# 3_waffling60-MX_mcu.net
KiCad netlist of a schematic drawn in Altium Designer
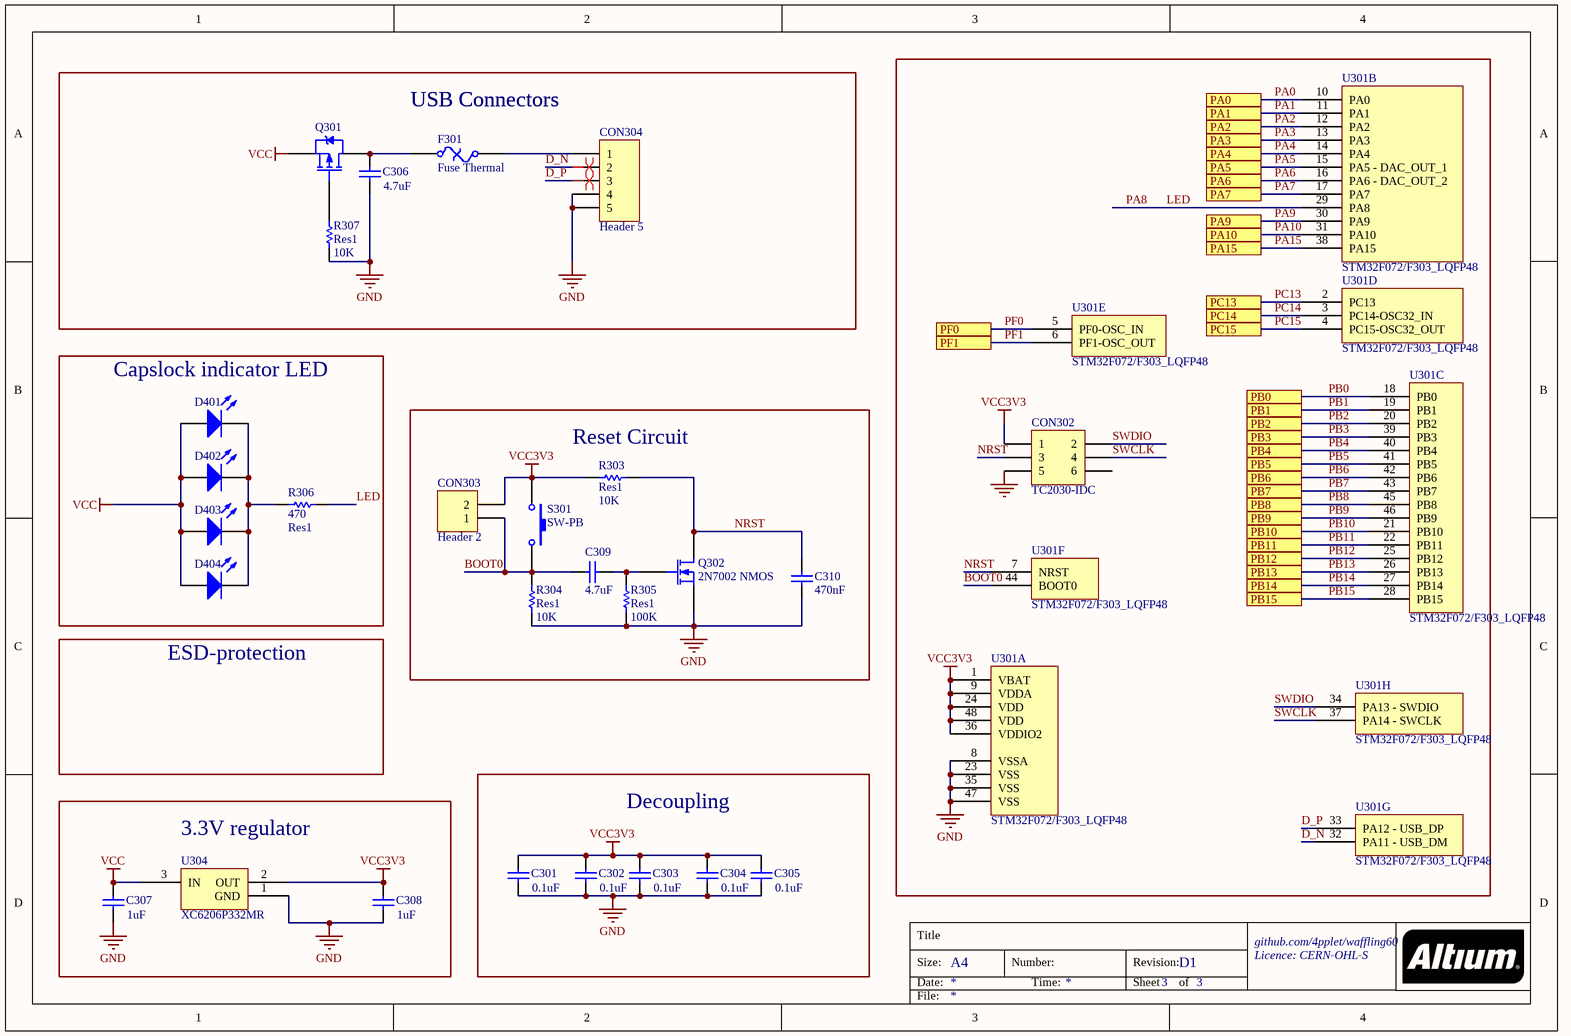
[diagram p0: 3_waffling60-MX_mcu.SchDoc]

(export (version "E")
  (design (tool "Eeschema 10.0.6"))
  (components
    (comp (ref "C301")
      (value "0.1uF")
      (footprint "C0603[1608]")
      (description "Capacitor")
      (fields (field (name "LCSC PART #") "C14663") (field (name "MRF.PART") "CC0603KRX7R9BB104"))
      (libsource (lib "Miscellaneous Devices") (part "Cap"))
    )
    (comp (ref "C302")
      (value "0.1uF")
      (footprint "C0603[1608]")
      (description "Capacitor")
      (fields (field (name "LCSC PART #") "C14663") (field (name "MRF.PART") "CC0603KRX7R9BB104"))
      (libsource (lib "Miscellaneous Devices") (part "Cap"))
    )
    (comp (ref "C303")
      (value "0.1uF")
      (footprint "C0603[1608]")
      (description "Capacitor")
      (fields (field (name "LCSC PART #") "C14663") (field (name "MRF.PART") "CC0603KRX7R9BB104"))
      (libsource (lib "Miscellaneous Devices") (part "Cap"))
    )
    (comp (ref "C304")
      (value "0.1uF")
      (footprint "C0603[1608]")
      (description "Capacitor")
      (fields (field (name "LCSC PART #") "C14663") (field (name "MRF.PART") "CC0603KRX7R9BB104"))
      (libsource (lib "Miscellaneous Devices") (part "Cap"))
    )
    (comp (ref "C305")
      (value "0.1uF")
      (footprint "C0603[1608]")
      (description "Capacitor")
      (fields (field (name "LCSC PART #") "C14663") (field (name "MRF.PART") "CC0603KRX7R9BB104"))
      (libsource (lib "Miscellaneous Devices") (part "Cap"))
    )
    (comp (ref "C306")
      (value "4.7uF")
      (footprint "C0603[1608]")
      (description "Capacitor")
      (fields (field (name "LCSC PART #") "C19666") (field (name "MRF.PART") "CL10A475KO8NNNC"))
      (libsource (lib "Miscellaneous Devices") (part "Cap"))
    )
    (comp (ref "C307")
      (value "1uF")
      (footprint "C0603[1608]")
      (description "Capacitor")
      (fields (field (name "LCSC PART #") "C15849") (field (name "MRF.PART") "CL10A105KB8NNNC"))
      (libsource (lib "Miscellaneous Devices") (part "Cap"))
    )
    (comp (ref "C308")
      (value "1uF")
      (footprint "C0603[1608]")
      (description "Capacitor")
      (fields (field (name "LCSC PART #") "C15849") (field (name "MRF.PART") "CL10A105KB8NNNC"))
      (libsource (lib "Miscellaneous Devices") (part "Cap"))
    )
    (comp (ref "C309")
      (value "4.7uF")
      (footprint "C0603[1608]")
      (description "Capacitor")
      (fields (field (name "LCSC PART #") "C19666") (field (name "MRF.PART") "CL10A475KO8NNNC"))
      (libsource (lib "Miscellaneous Devices") (part "Cap"))
    )
    (comp (ref "C310")
      (value "470nF")
      (footprint "C0603[1608]")
      (description "Capacitor")
      (fields (field (name "LCSC PART #") "C1623") (field (name "MRF.PART") "CL10B474KA8NNNC"))
      (libsource (lib "Miscellaneous Devices") (part "Cap"))
    )
    (comp (ref "CON302")
      (value "TC2030-IDC")
      (footprint "TC2030-IDC-NL")
      (description "Header, 3-Pin, Dual row")
      (libsource (lib "Miscellaneous Connectors") (part "Header 3X2"))
    )
    (comp (ref "CON303")
      (value "Header 2")
      (footprint "HDR1X2")
      (description "Header, 2-Pin")
      (libsource (lib "Miscellaneous Connectors") (part "Header 2"))
    )
    (comp (ref "CON304")
      (value "Header 5")
      (footprint "JST SM04B-SRSS-TB")
      (description "JST for USB daughter board")
      (fields (field (name "LCSC PART #") "C160404") (field (name "MRF.PART") "SM04B-SRSS-TB(LF)(SN)"))
      (libsource (lib "Miscellaneous Connectors") (part "Header 5"))
    )
    (comp (ref "D401")
      (value "CAPS_LED")
      (footprint "SWITCH_LED - 1U")
      (libsource (lib "Simulation Generic Components") (part "LED"))
    )
    (comp (ref "D402")
      (value "CAPS_LED")
      (footprint "SWITCH_LED - 1U")
      (libsource (lib "Simulation Generic Components") (part "LED"))
    )
    (comp (ref "D403")
      (value "CAPS_LED")
      (footprint "SWITCH_LED - 1U")
      (libsource (lib "Simulation Generic Components") (part "LED"))
    )
    (comp (ref "D404")
      (value "CAPS_LED")
      (footprint "SWITCH_LED - 1U")
      (libsource (lib "Simulation Generic Components") (part "LED"))
    )
    (comp (ref "F301")
      (value "Fuse Thermal")
      (footprint "C1206[3216]")
      (description "Thermal Fuse")
      (fields (field (name "LCSC PART #") "C135338") (field (name "MRF.PART") "ASMD1206-050"))
      (libsource (lib "Miscellaneous Devices") (part "Fuse Thermal"))
    )
    (comp (ref "Q301")
      (value "PMOS-2")
      (footprint "SOT-23-3")
      (description "P-Channel Power MOSFET")
      (fields (field (name "LCSC PART #") "C10487") (field (name "MRF.PART") "SI2301CDS-T1-GE3"))
      (libsource (lib "Miscellaneous Devices") (part "PMOS-2"))
    )
    (comp (ref "Q302")
      (value "2N7002 NMOS")
      (footprint "SOT-23-3")
      (description "N-Channel MOSFET")
      (fields (field (name "LCSC PART #") "C8545") (field (name "MRF.PART") "2N7002"))
      (libsource (lib "Miscellaneous Devices") (part "MOSFET-N"))
    )
    (comp (ref "R303")
      (value "Res1")
      (footprint "R0603[1608]")
      (description "Resistor")
      (fields
        (field (name "ALTIUM_VALUE") "10K")
        (field (name "LCSC PART #") "C25804")
        (field (name "MRF.PART") "0603WAF1002T5E")
      )
      (libsource (lib "Miscellaneous Devices") (part "Res1"))
    )
    (comp (ref "R304")
      (value "Res1")
      (footprint "R0603[1608]")
      (description "Resistor")
      (fields
        (field (name "ALTIUM_VALUE") "10K")
        (field (name "LCSC PART #") "C25804")
        (field (name "MRF.PART") "0603WAF1002T5E")
      )
      (libsource (lib "Miscellaneous Devices") (part "Res1"))
    )
    (comp (ref "R305")
      (value "Res1")
      (footprint "R0603[1608]")
      (description "Resistor")
      (fields
        (field (name "ALTIUM_VALUE") "100K")
        (field (name "LCSC PART #") "C25803")
        (field (name "MRF.PART") "0603WAF1003T5E")
      )
      (libsource (lib "Miscellaneous Devices") (part "Res1"))
    )
    (comp (ref "R306")
      (value "Res1")
      (footprint "R0603[1608]")
      (description "Resistor")
      (fields
        (field (name "ALTIUM_VALUE") "470")
        (field (name "LCSC PART #") "C25804")
        (field (name "MRF.PART") "0603WAF1002T5E")
      )
      (libsource (lib "Miscellaneous Devices") (part "Res1"))
    )
    (comp (ref "R307")
      (value "Res1")
      (footprint "R0603[1608]")
      (description "Resistor")
      (fields
        (field (name "ALTIUM_VALUE") "10K")
        (field (name "LCSC PART #") "C25804")
        (field (name "MRF.PART") "0603WAF1002T5E")
      )
      (libsource (lib "Miscellaneous Devices") (part "Res1"))
    )
    (comp (ref "S301")
      (value "SW-PB")
      (footprint "XKB Switch")
      (description "Switch")
      (fields (field (name "MRF.PART") "TS-1187A-C-D-B") (field (name "LCSC PART #") "C318888"))
      (libsource (lib "Miscellaneous Devices") (part "SW-PB"))
    )
    (comp (ref "U301")
      (value "STM32F072/F303_LQFP48")
      (footprint "STM32 - COMBO 7X7MM")
      (fields (field (name "LCSC PART #") "C915660") (field (name "MRF.PART") "APM32F072CBT6"))
      (libsource (lib "Keebs") (part "STM32F072/F303_LQFP48"))
    )
    (comp (ref "U304")
      (value "XC6206P332MR")
      (footprint "SOT-23-3")
      (fields (field (name "LCSC PART #") "C5446"))
      (libsource (lib "Keebs") (part "SOT23 LDO"))
    )
  )
  (nets
    (net (code "1") (name "/BOOT0") (class "Default")
      (node (ref "C309") (pin "1") (pinfunction "1_1") (pintype "passive"))
      (node (ref "CON303") (pin "1") (pinfunction "1_1") (pintype "passive"))
      (node (ref "R304") (pin "1") (pinfunction "1_1") (pintype "passive"))
      (node (ref "S301") (pin "2") (pinfunction "2_2") (pintype "passive"))
      (node (ref "U301") (pin "44") (pinfunction "BOOT0_44") (pintype "passive"))
    )
    (net (code "2") (name "/D_N") (class "Default")
      (node (ref "CON304") (pin "2") (pinfunction "2_2") (pintype "passive"))
      (node (ref "U301") (pin "32") (pinfunction "PA11_-_USB_DM_32") (pintype "passive"))
    )
    (net (code "3") (name "/D_P") (class "Default")
      (node (ref "CON304") (pin "3") (pinfunction "3_3") (pintype "passive"))
      (node (ref "U301") (pin "33") (pinfunction "PA12_-_USB_DP_33") (pintype "passive"))
    )
    (net (code "4") (name "/LED") (class "Default")
      (node (ref "R306") (pin "1") (pinfunction "1_1") (pintype "passive"))
      (node (ref "U301") (pin "29") (pinfunction "PA8_29") (pintype "passive"))
    )
    (net (code "5") (name "/NRST") (class "Default")
      (node (ref "C310") (pin "1") (pinfunction "1_1") (pintype "passive"))
      (node (ref "CON302") (pin "3") (pinfunction "3_3") (pintype "passive"))
      (node (ref "Q302") (pin "3") (pinfunction "D_3") (pintype "passive"))
      (node (ref "R303") (pin "2") (pinfunction "2_2") (pintype "passive"))
      (node (ref "U301") (pin "7") (pinfunction "NRST_7") (pintype "passive"))
    )
    (net (code "6") (name "/PA0") (class "Default")
      (node (ref "U301") (pin "10") (pinfunction "PA0_10") (pintype "passive"))
    )
    (net (code "7") (name "/PA1") (class "Default")
      (node (ref "U301") (pin "11") (pinfunction "PA1_11") (pintype "passive"))
    )
    (net (code "8") (name "/PA2") (class "Default")
      (node (ref "U301") (pin "12") (pinfunction "PA2_12") (pintype "passive"))
    )
    (net (code "9") (name "/PA3") (class "Default")
      (node (ref "U301") (pin "13") (pinfunction "PA3_13") (pintype "passive"))
    )
    (net (code "10") (name "/PA4") (class "Default")
      (node (ref "U301") (pin "14") (pinfunction "PA4_14") (pintype "passive"))
    )
    (net (code "11") (name "/PA5") (class "Default")
      (node (ref "U301") (pin "15") (pinfunction "PA5_-_DAC_OUT_1_15") (pintype "passive"))
    )
    (net (code "12") (name "/PA6") (class "Default")
      (node (ref "U301") (pin "16") (pinfunction "PA6_-_DAC_OUT_2_16") (pintype "passive"))
    )
    (net (code "13") (name "/PA7") (class "Default")
      (node (ref "U301") (pin "17") (pinfunction "PA7_17") (pintype "passive"))
    )
    (net (code "14") (name "/PA9") (class "Default")
      (node (ref "U301") (pin "30") (pinfunction "PA9_30") (pintype "passive"))
    )
    (net (code "15") (name "/PA10") (class "Default")
      (node (ref "U301") (pin "31") (pinfunction "PA10_31") (pintype "passive"))
    )
    (net (code "16") (name "/PA15") (class "Default")
      (node (ref "U301") (pin "38") (pinfunction "PA15_38") (pintype "passive"))
    )
    (net (code "17") (name "/PB0") (class "Default")
      (node (ref "U301") (pin "18") (pinfunction "PB0_18") (pintype "passive"))
    )
    (net (code "18") (name "/PB1") (class "Default")
      (node (ref "U301") (pin "19") (pinfunction "PB1_19") (pintype "passive"))
    )
    (net (code "19") (name "/PB2") (class "Default")
      (node (ref "U301") (pin "20") (pinfunction "PB2_20") (pintype "passive"))
    )
    (net (code "20") (name "/PB3") (class "Default")
      (node (ref "U301") (pin "39") (pinfunction "PB3_39") (pintype "passive"))
    )
    (net (code "21") (name "/PB4") (class "Default")
      (node (ref "U301") (pin "40") (pinfunction "PB4_40") (pintype "passive"))
    )
    (net (code "22") (name "/PB5") (class "Default")
      (node (ref "U301") (pin "41") (pinfunction "PB5_41") (pintype "passive"))
    )
    (net (code "23") (name "/PB6") (class "Default")
      (node (ref "U301") (pin "42") (pinfunction "PB6_42") (pintype "passive"))
    )
    (net (code "24") (name "/PB7") (class "Default")
      (node (ref "U301") (pin "43") (pinfunction "PB7_43") (pintype "passive"))
    )
    (net (code "25") (name "/PB8") (class "Default")
      (node (ref "U301") (pin "45") (pinfunction "PB8_45") (pintype "passive"))
    )
    (net (code "26") (name "/PB9") (class "Default")
      (node (ref "U301") (pin "46") (pinfunction "PB9_46") (pintype "passive"))
    )
    (net (code "27") (name "/PB10") (class "Default")
      (node (ref "U301") (pin "21") (pinfunction "PB10_21") (pintype "passive"))
    )
    (net (code "28") (name "/PB11") (class "Default")
      (node (ref "U301") (pin "22") (pinfunction "PB11_22") (pintype "passive"))
    )
    (net (code "29") (name "/PB12") (class "Default")
      (node (ref "U301") (pin "25") (pinfunction "PB12_25") (pintype "passive"))
    )
    (net (code "30") (name "/PB13") (class "Default")
      (node (ref "U301") (pin "26") (pinfunction "PB13_26") (pintype "passive"))
    )
    (net (code "31") (name "/PB14") (class "Default")
      (node (ref "U301") (pin "27") (pinfunction "PB14_27") (pintype "passive"))
    )
    (net (code "32") (name "/PB15") (class "Default")
      (node (ref "U301") (pin "28") (pinfunction "PB15_28") (pintype "passive"))
    )
    (net (code "33") (name "/PC13") (class "Default")
      (node (ref "U301") (pin "2") (pinfunction "PC13_2") (pintype "passive"))
    )
    (net (code "34") (name "/PC14") (class "Default")
      (node (ref "U301") (pin "3") (pinfunction "PC14-OSC32_IN_3") (pintype "passive"))
    )
    (net (code "35") (name "/PC15") (class "Default")
      (node (ref "U301") (pin "4") (pinfunction "PC15-OSC32_OUT_4") (pintype "passive"))
    )
    (net (code "36") (name "/PF0") (class "Default")
      (node (ref "U301") (pin "5") (pinfunction "PF0-OSC_IN_5") (pintype "passive"))
    )
    (net (code "37") (name "/PF1") (class "Default")
      (node (ref "U301") (pin "6") (pinfunction "PF1-OSC_OUT_6") (pintype "passive"))
    )
    (net (code "38") (name "/SWCLK") (class "Default")
      (node (ref "CON302") (pin "4") (pinfunction "4_4") (pintype "passive"))
      (node (ref "U301") (pin "37") (pinfunction "PA14_-_SWCLK_37") (pintype "passive"))
    )
    (net (code "39") (name "/SWDIO") (class "Default")
      (node (ref "CON302") (pin "2") (pinfunction "2_2") (pintype "passive"))
      (node (ref "U301") (pin "34") (pinfunction "PA13_-_SWDIO_34") (pintype "passive"))
    )
    (net (code "40") (name "GND") (class "Default")
      (node (ref "C301") (pin "1") (pinfunction "1_1") (pintype "passive"))
      (node (ref "C302") (pin "1") (pinfunction "1_1") (pintype "passive"))
      (node (ref "C303") (pin "1") (pinfunction "1_1") (pintype "passive"))
      (node (ref "C304") (pin "1") (pinfunction "1_1") (pintype "passive"))
      (node (ref "C305") (pin "1") (pinfunction "1_1") (pintype "passive"))
      (node (ref "C306") (pin "1") (pinfunction "1_1") (pintype "passive"))
      (node (ref "C307") (pin "1") (pinfunction "1_1") (pintype "passive"))
      (node (ref "C308") (pin "1") (pinfunction "1_1") (pintype "passive"))
      (node (ref "C310") (pin "2") (pinfunction "2_2") (pintype "passive"))
      (node (ref "CON302") (pin "5") (pinfunction "5_5") (pintype "passive"))
      (node (ref "CON304") (pin "4") (pinfunction "4_4") (pintype "passive"))
      (node (ref "CON304") (pin "5") (pinfunction "5_5") (pintype "passive"))
      (node (ref "Q302") (pin "2") (pinfunction "S_2") (pintype "passive"))
      (node (ref "R304") (pin "2") (pinfunction "2_2") (pintype "passive"))
      (node (ref "R305") (pin "2") (pinfunction "2_2") (pintype "passive"))
      (node (ref "R307") (pin "2") (pinfunction "2_2") (pintype "passive"))
      (node (ref "U301") (pin "23") (pinfunction "VSS_23") (pintype "passive"))
      (node (ref "U301") (pin "35") (pinfunction "VSS_35") (pintype "passive"))
      (node (ref "U301") (pin "47") (pinfunction "VSS_47") (pintype "passive"))
      (node (ref "U301") (pin "8") (pinfunction "VSSA_8") (pintype "passive"))
      (node (ref "U304") (pin "1") (pinfunction "GND_1") (pintype "passive"))
    )
    (net (code "41") (name "Net-(CON304-Pad1)") (class "Default")
      (node (ref "CON304") (pin "1") (pinfunction "1_1") (pintype "passive"))
      (node (ref "F301") (pin "2") (pinfunction "2_2") (pintype "passive"))
    )
    (net (code "42") (name "Net-(D401-K)") (class "Default")
      (node (ref "D401") (pin "2") (pinfunction "K_2") (pintype "passive"))
      (node (ref "D402") (pin "2") (pinfunction "K_2") (pintype "passive"))
      (node (ref "D403") (pin "2") (pinfunction "K_2") (pintype "passive"))
      (node (ref "D404") (pin "2") (pinfunction "K_2") (pintype "passive"))
      (node (ref "R306") (pin "2") (pinfunction "2_2") (pintype "passive"))
    )
    (net (code "43") (name "Net-(Q301-D)") (class "Default")
      (node (ref "C306") (pin "2") (pinfunction "2_2") (pintype "passive"))
      (node (ref "F301") (pin "1") (pinfunction "1_1") (pintype "passive"))
      (node (ref "Q301") (pin "3") (pinfunction "D_3") (pintype "passive"))
    )
    (net (code "44") (name "Net-(Q301-G)") (class "Default")
      (node (ref "Q301") (pin "1") (pinfunction "G_1") (pintype "passive"))
      (node (ref "R307") (pin "1") (pinfunction "1_1") (pintype "passive"))
    )
    (net (code "45") (name "Net-(Q302-G)") (class "Default")
      (node (ref "C309") (pin "2") (pinfunction "2_2") (pintype "passive"))
      (node (ref "Q302") (pin "1") (pinfunction "G_1") (pintype "passive"))
      (node (ref "R305") (pin "1") (pinfunction "1_1") (pintype "passive"))
    )
    (net (code "46") (name "VCC") (class "Default")
      (node (ref "C307") (pin "2") (pinfunction "2_2") (pintype "passive"))
      (node (ref "D401") (pin "1") (pinfunction "A_1") (pintype "passive"))
      (node (ref "D402") (pin "1") (pinfunction "A_1") (pintype "passive"))
      (node (ref "D403") (pin "1") (pinfunction "A_1") (pintype "passive"))
      (node (ref "D404") (pin "1") (pinfunction "A_1") (pintype "passive"))
      (node (ref "Q301") (pin "2") (pinfunction "S_2") (pintype "passive"))
      (node (ref "U304") (pin "3") (pinfunction "IN_3") (pintype "passive"))
    )
    (net (code "47") (name "VCC3V3") (class "Default")
      (node (ref "C301") (pin "2") (pinfunction "2_2") (pintype "passive"))
      (node (ref "C302") (pin "2") (pinfunction "2_2") (pintype "passive"))
      (node (ref "C303") (pin "2") (pinfunction "2_2") (pintype "passive"))
      (node (ref "C304") (pin "2") (pinfunction "2_2") (pintype "passive"))
      (node (ref "C305") (pin "2") (pinfunction "2_2") (pintype "passive"))
      (node (ref "C308") (pin "2") (pinfunction "2_2") (pintype "passive"))
      (node (ref "CON302") (pin "1") (pinfunction "1_1") (pintype "passive"))
      (node (ref "CON303") (pin "2") (pinfunction "2_2") (pintype "passive"))
      (node (ref "R303") (pin "1") (pinfunction "1_1") (pintype "passive"))
      (node (ref "S301") (pin "1") (pinfunction "1_1") (pintype "passive"))
      (node (ref "U301") (pin "1") (pinfunction "VBAT_1") (pintype "passive"))
      (node (ref "U301") (pin "24") (pinfunction "VDD_24") (pintype "passive"))
      (node (ref "U301") (pin "36") (pinfunction "VDDIO2_36") (pintype "passive"))
      (node (ref "U301") (pin "48") (pinfunction "VDD_48") (pintype "passive"))
      (node (ref "U301") (pin "9") (pinfunction "VDDA_9") (pintype "passive"))
      (node (ref "U304") (pin "2") (pinfunction "OUT_2") (pintype "passive"))
    )
    (net (code "48") (name "unconnected-(CON302-Pad6)") (class "Default")
      (node (ref "CON302") (pin "6") (pinfunction "6_6") (pintype "passive"))
    )
  )
)
